# M700E.net
KiCad netlist of a schematic drawn in EAGLE
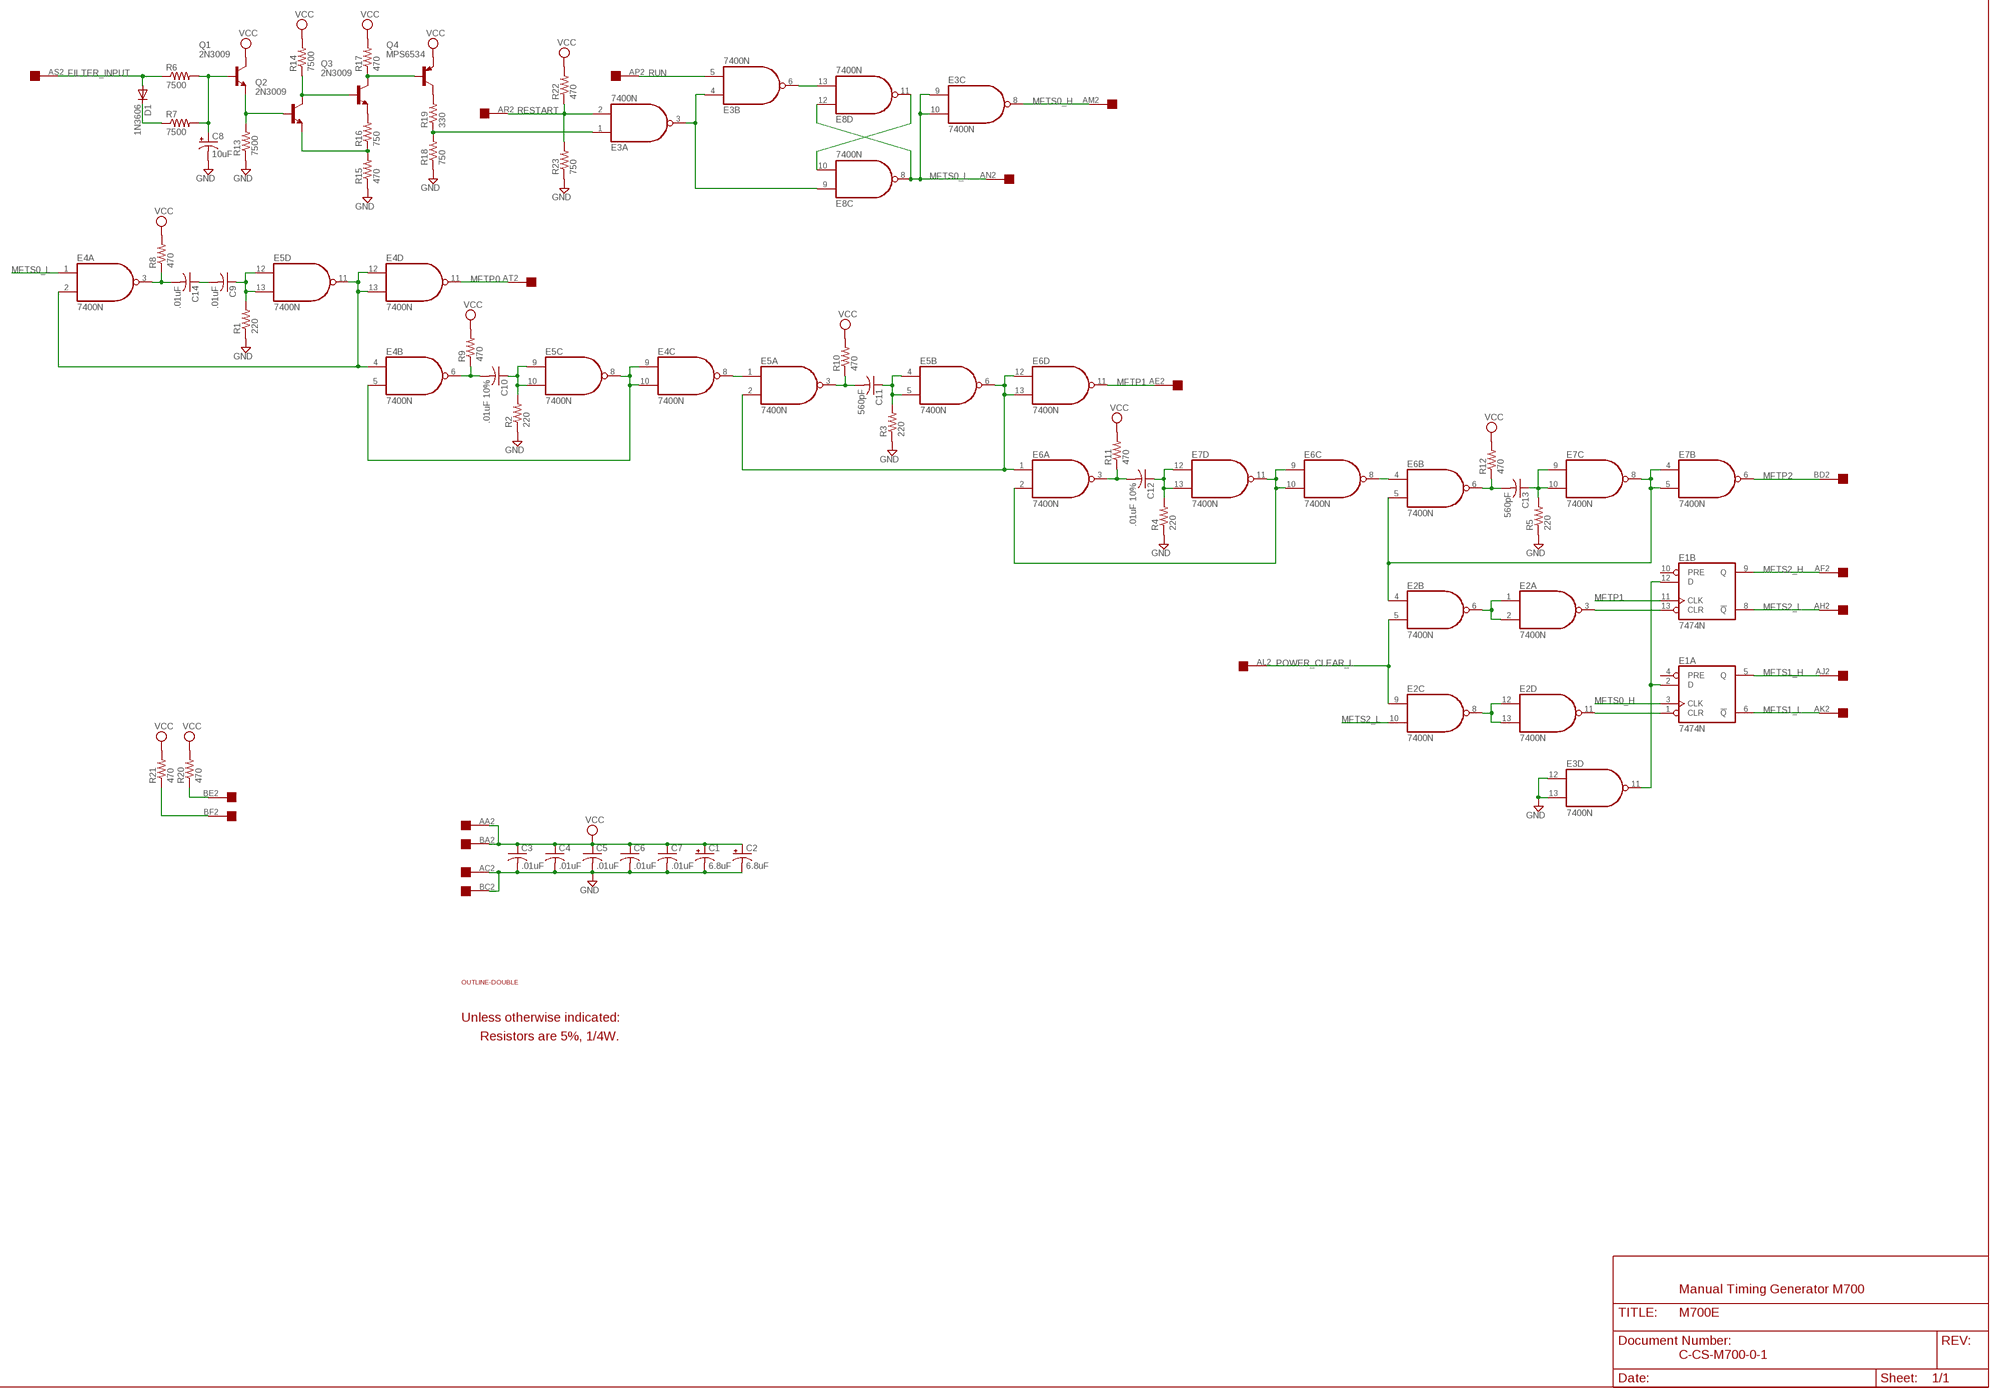
[diagram p0: schematic, sheet 1]

(export (version "E")
  (design (tool "Eeschema 10.0.6"))
  (components
    (comp (ref "C1")
      (value "6.8uF")
      (footprint "eagle-import:E12-8")
      (libsource (lib "eagle-import") (part "CPOL-USE20-8AXIAL"))
    )
    (comp (ref "C2")
      (value "6.8uF")
      (footprint "eagle-import:E12-8")
      (libsource (lib "eagle-import") (part "CPOL-USE20-8AXIAL"))
    )
    (comp (ref "C3")
      (value ".01uF")
      (footprint "eagle-import:C050-025X075")
      (libsource (lib "eagle-import") (part "C-US050-025X075"))
    )
    (comp (ref "C4")
      (value ".01uF")
      (footprint "eagle-import:C050-025X075")
      (libsource (lib "eagle-import") (part "C-US050-025X075"))
    )
    (comp (ref "C5")
      (value ".01uF")
      (footprint "eagle-import:C050-025X075")
      (libsource (lib "eagle-import") (part "C-US050-025X075"))
    )
    (comp (ref "C6")
      (value ".01uF")
      (footprint "eagle-import:C050-025X075")
      (libsource (lib "eagle-import") (part "C-US050-025X075"))
    )
    (comp (ref "C7")
      (value ".01uF")
      (footprint "eagle-import:C050-025X075")
      (libsource (lib "eagle-import") (part "C-US050-025X075"))
    )
    (comp (ref "C8")
      (value "10uF")
      (footprint "eagle-import:E12-8")
      (libsource (lib "eagle-import") (part "CPOL-USE20-8AXIAL"))
    )
    (comp (ref "C9")
      (value ".01uF")
      (footprint "eagle-import:C150-054X183")
      (libsource (lib "eagle-import") (part "C-US150-054X183"))
    )
    (comp (ref "C10")
      (value ".01uF 10%")
      (footprint "eagle-import:C150-054X183")
      (libsource (lib "eagle-import") (part "C-US150-054X183"))
    )
    (comp (ref "C11")
      (value "560pF")
      (footprint "eagle-import:C050-025X075")
      (libsource (lib "eagle-import") (part "C-US050-025X075"))
    )
    (comp (ref "C12")
      (value ".01uF 10%")
      (footprint "eagle-import:C150-054X183")
      (libsource (lib "eagle-import") (part "C-US150-054X183"))
    )
    (comp (ref "C13")
      (value "560pF")
      (footprint "eagle-import:C050-025X075")
      (libsource (lib "eagle-import") (part "C-US050-025X075"))
    )
    (comp (ref "C14")
      (value ".01uF")
      (footprint "eagle-import:C150-054X183")
      (libsource (lib "eagle-import") (part "C-US150-054X183"))
    )
    (comp (ref "D1")
      (value "1N3606")
      (footprint "eagle-import:DO35-10")
      (libsource (lib "eagle-import") (part "1N4148DO35-10"))
    )
    (comp (ref "E1")
      (value "7474N")
      (footprint "eagle-import:DIL14")
      (libsource (lib "eagle-import") (part "7474NS"))
    )
    (comp (ref "E2")
      (value "7400N")
      (footprint "eagle-import:DIL14")
      (libsource (lib "eagle-import") (part "7400N"))
    )
    (comp (ref "E3")
      (value "7400N")
      (footprint "eagle-import:DIL14")
      (libsource (lib "eagle-import") (part "7400N"))
    )
    (comp (ref "E4")
      (value "7400N")
      (footprint "eagle-import:DIL14")
      (libsource (lib "eagle-import") (part "7400N"))
    )
    (comp (ref "E5")
      (value "7400N")
      (footprint "eagle-import:DIL14")
      (libsource (lib "eagle-import") (part "7400N"))
    )
    (comp (ref "E6")
      (value "7400N")
      (footprint "eagle-import:DIL14")
      (libsource (lib "eagle-import") (part "7400N"))
    )
    (comp (ref "E7")
      (value "7400N")
      (footprint "eagle-import:DIL14")
      (libsource (lib "eagle-import") (part "7400N"))
    )
    (comp (ref "E8")
      (value "7400N")
      (footprint "eagle-import:DIL14")
      (libsource (lib "eagle-import") (part "7400N"))
    )
    (comp (ref "Q1")
      (value "2N3009")
      (footprint "eagle-import:TO5")
      (libsource (lib "eagle-import") (part "2N2102"))
    )
    (comp (ref "Q2")
      (value "2N3009")
      (footprint "eagle-import:TO5")
      (libsource (lib "eagle-import") (part "2N2102"))
    )
    (comp (ref "Q3")
      (value "2N3009")
      (footprint "eagle-import:TO5")
      (libsource (lib "eagle-import") (part "2N2102"))
    )
    (comp (ref "Q4")
      (value "MPS6534")
      (footprint "eagle-import:TO5")
      (libsource (lib "eagle-import") (part "2N2905"))
    )
    (comp (ref "R1")
      (value "220")
      (footprint "eagle-import:0207_10")
      (libsource (lib "eagle-import") (part "R-US_0207/10"))
    )
    (comp (ref "R2")
      (value "220")
      (footprint "eagle-import:0207_10")
      (libsource (lib "eagle-import") (part "R-US_0207/10"))
    )
    (comp (ref "R3")
      (value "220")
      (footprint "eagle-import:0207_10")
      (libsource (lib "eagle-import") (part "R-US_0207/10"))
    )
    (comp (ref "R4")
      (value "220")
      (footprint "eagle-import:0207_10")
      (libsource (lib "eagle-import") (part "R-US_0207/10"))
    )
    (comp (ref "R5")
      (value "220")
      (footprint "eagle-import:0207_10")
      (libsource (lib "eagle-import") (part "R-US_0207/10"))
    )
    (comp (ref "R6")
      (value "7500")
      (footprint "eagle-import:0207_10")
      (libsource (lib "eagle-import") (part "R-US_0207/10"))
    )
    (comp (ref "R7")
      (value "7500")
      (footprint "eagle-import:0207_10")
      (libsource (lib "eagle-import") (part "R-US_0207/10"))
    )
    (comp (ref "R8")
      (value "470")
      (footprint "eagle-import:0207_10")
      (libsource (lib "eagle-import") (part "R-US_0207/10"))
    )
    (comp (ref "R9")
      (value "470")
      (footprint "eagle-import:0207_10")
      (libsource (lib "eagle-import") (part "R-US_0207/10"))
    )
    (comp (ref "R10")
      (value "470")
      (footprint "eagle-import:0207_10")
      (libsource (lib "eagle-import") (part "R-US_0207/10"))
    )
    (comp (ref "R11")
      (value "470")
      (footprint "eagle-import:0207_10")
      (libsource (lib "eagle-import") (part "R-US_0207/10"))
    )
    (comp (ref "R12")
      (value "470")
      (footprint "eagle-import:0207_10")
      (libsource (lib "eagle-import") (part "R-US_0207/10"))
    )
    (comp (ref "R13")
      (value "7500")
      (footprint "eagle-import:0207_10")
      (libsource (lib "eagle-import") (part "R-US_0207/10"))
    )
    (comp (ref "R14")
      (value "7500")
      (footprint "eagle-import:0207_10")
      (libsource (lib "eagle-import") (part "R-US_0207/10"))
    )
    (comp (ref "R15")
      (value "470")
      (footprint "eagle-import:0207_10")
      (libsource (lib "eagle-import") (part "R-US_0207/10"))
    )
    (comp (ref "R16")
      (value "750")
      (footprint "eagle-import:0207_10")
      (libsource (lib "eagle-import") (part "R-US_0207/10"))
    )
    (comp (ref "R17")
      (value "470")
      (footprint "eagle-import:0207_10")
      (libsource (lib "eagle-import") (part "R-US_0207/10"))
    )
    (comp (ref "R18")
      (value "750")
      (footprint "eagle-import:0207_10")
      (libsource (lib "eagle-import") (part "R-US_0207/10"))
    )
    (comp (ref "R19")
      (value "330")
      (footprint "eagle-import:0207_10")
      (libsource (lib "eagle-import") (part "R-US_0207/10"))
    )
    (comp (ref "R20")
      (value "470")
      (footprint "eagle-import:0207_10")
      (libsource (lib "eagle-import") (part "R-US_0207/10"))
    )
    (comp (ref "R21")
      (value "470")
      (footprint "eagle-import:0207_10")
      (libsource (lib "eagle-import") (part "R-US_0207/10"))
    )
    (comp (ref "R22")
      (value "470")
      (footprint "eagle-import:0207_10")
      (libsource (lib "eagle-import") (part "R-US_0207/10"))
    )
    (comp (ref "R23")
      (value "750")
      (footprint "eagle-import:0207_10")
      (libsource (lib "eagle-import") (part "R-US_0207/10"))
    )
    (comp (ref "U$1")
      (value "DOUBLE")
      (footprint "eagle-import:EDGE-CON4")
      (libsource (lib "eagle-import") (part "DOUBLE"))
    )
    (comp (ref "U$2")
      (value "OUTLINE-DOUBLE")
      (footprint "eagle-import:DOUBLE")
      (libsource (lib "eagle-import") (part "OUTLINE-DOUBLE"))
    )
  )
  (nets
    (net (code "1") (name "/FILTER_INPUT") (class "Default")
      (node (ref "D1") (pin "A") (pinfunction "A_A") (pintype "passive"))
      (node (ref "R6") (pin "1") (pinfunction "1_1") (pintype "passive"))
      (node (ref "U$1") (pin "AS2") (pinfunction "1_AS2") (pintype "bidirectional"))
    )
    (net (code "2") (name "/MFTP0") (class "Default")
      (node (ref "E4") (pin "11") (pinfunction "O_11") (pintype "output"))
      (node (ref "U$1") (pin "AT2") (pinfunction "1_AT2") (pintype "bidirectional"))
    )
    (net (code "3") (name "/MFTP1") (class "Default")
      (node (ref "E1") (pin "11") (pinfunction "CLK_11") (pintype "input"))
      (node (ref "E6") (pin "11") (pinfunction "O_11") (pintype "output"))
      (node (ref "U$1") (pin "AE2") (pinfunction "1_AE2") (pintype "bidirectional"))
    )
    (net (code "4") (name "/MFTP2") (class "Default")
      (node (ref "E7") (pin "6") (pinfunction "O_6") (pintype "output"))
      (node (ref "U$1") (pin "BD2") (pinfunction "1_BD2") (pintype "bidirectional"))
    )
    (net (code "5") (name "/MFTS0_H") (class "Default")
      (node (ref "E1") (pin "3") (pinfunction "CLK_3") (pintype "input"))
      (node (ref "E3") (pin "8") (pinfunction "O_8") (pintype "output"))
      (node (ref "U$1") (pin "AM2") (pinfunction "1_AM2") (pintype "bidirectional"))
    )
    (net (code "6") (name "/MFTS0_L") (class "Default")
      (node (ref "E3") (pin "10") (pinfunction "I1_10") (pintype "input"))
      (node (ref "E3") (pin "9") (pinfunction "I0_9") (pintype "input"))
      (node (ref "E4") (pin "1") (pinfunction "I0_1") (pintype "input"))
      (node (ref "E8") (pin "12") (pinfunction "I0_12") (pintype "input"))
      (node (ref "E8") (pin "8") (pinfunction "O_8") (pintype "output"))
      (node (ref "U$1") (pin "AN2") (pinfunction "1_AN2") (pintype "bidirectional"))
    )
    (net (code "7") (name "/MFTS1_H") (class "Default")
      (node (ref "E1") (pin "5") (pinfunction "Q_5") (pintype "output"))
      (node (ref "U$1") (pin "AJ2") (pinfunction "1_AJ2") (pintype "bidirectional"))
    )
    (net (code "8") (name "/MFTS1_L") (class "Default")
      (node (ref "E1") (pin "6") (pinfunction "~{Q}_6") (pintype "output"))
      (node (ref "U$1") (pin "AK2") (pinfunction "1_AK2") (pintype "bidirectional"))
    )
    (net (code "9") (name "/MFTS2_H") (class "Default")
      (node (ref "E1") (pin "9") (pinfunction "Q_9") (pintype "output"))
      (node (ref "U$1") (pin "AF2") (pinfunction "1_AF2") (pintype "bidirectional"))
    )
    (net (code "10") (name "/MFTS2_L") (class "Default")
      (node (ref "E1") (pin "8") (pinfunction "~{Q}_8") (pintype "output"))
      (node (ref "E2") (pin "10") (pinfunction "I1_10") (pintype "input"))
      (node (ref "U$1") (pin "AH2") (pinfunction "1_AH2") (pintype "bidirectional"))
    )
    (net (code "11") (name "/POWER_CLEAR_L") (class "Default")
      (node (ref "E2") (pin "5") (pinfunction "I1_5") (pintype "input"))
      (node (ref "E2") (pin "9") (pinfunction "I0_9") (pintype "input"))
      (node (ref "U$1") (pin "AL2") (pinfunction "1_AL2") (pintype "bidirectional"))
    )
    (net (code "12") (name "/RESTART") (class "Default")
      (node (ref "E3") (pin "2") (pinfunction "I1_2") (pintype "input"))
      (node (ref "R22") (pin "1") (pinfunction "1_1") (pintype "passive"))
      (node (ref "R23") (pin "2") (pinfunction "2_2") (pintype "passive"))
      (node (ref "U$1") (pin "AR2") (pinfunction "1_AR2") (pintype "bidirectional"))
    )
    (net (code "13") (name "/RUN") (class "Default")
      (node (ref "E3") (pin "5") (pinfunction "I1_5") (pintype "input"))
      (node (ref "U$1") (pin "AP2") (pinfunction "1_AP2") (pintype "bidirectional"))
    )
    (net (code "14") (name "GND") (class "Default")
      (node (ref "C1") (pin "-") (pinfunction "-_-") (pintype "passive"))
      (node (ref "C2") (pin "-") (pinfunction "-_-") (pintype "passive"))
      (node (ref "C3") (pin "2") (pinfunction "2_2") (pintype "passive"))
      (node (ref "C4") (pin "2") (pinfunction "2_2") (pintype "passive"))
      (node (ref "C5") (pin "2") (pinfunction "2_2") (pintype "passive"))
      (node (ref "C6") (pin "2") (pinfunction "2_2") (pintype "passive"))
      (node (ref "C7") (pin "2") (pinfunction "2_2") (pintype "passive"))
      (node (ref "C8") (pin "-") (pinfunction "-_-") (pintype "passive"))
      (node (ref "E3") (pin "12") (pinfunction "I0_12") (pintype "input"))
      (node (ref "E3") (pin "13") (pinfunction "I1_13") (pintype "input"))
      (node (ref "R1") (pin "1") (pinfunction "1_1") (pintype "passive"))
      (node (ref "R13") (pin "1") (pinfunction "1_1") (pintype "passive"))
      (node (ref "R15") (pin "1") (pinfunction "1_1") (pintype "passive"))
      (node (ref "R18") (pin "1") (pinfunction "1_1") (pintype "passive"))
      (node (ref "R2") (pin "1") (pinfunction "1_1") (pintype "passive"))
      (node (ref "R23") (pin "1") (pinfunction "1_1") (pintype "passive"))
      (node (ref "R3") (pin "1") (pinfunction "1_1") (pintype "passive"))
      (node (ref "R4") (pin "1") (pinfunction "1_1") (pintype "passive"))
      (node (ref "R5") (pin "1") (pinfunction "1_1") (pintype "passive"))
      (node (ref "U$1") (pin "AC2") (pinfunction "1_AC2") (pintype "bidirectional"))
      (node (ref "U$1") (pin "BC2") (pinfunction "1_BC2") (pintype "bidirectional"))
    )
    (net (code "15") (name "Net-(C14-Pad1)") (class "Default")
      (node (ref "C14") (pin "1") (pinfunction "1_1") (pintype "passive"))
      (node (ref "C9") (pin "2") (pinfunction "2_2") (pintype "passive"))
    )
    (net (code "16") (name "Net-(D1-PadC)") (class "Default")
      (node (ref "D1") (pin "C") (pinfunction "C_C") (pintype "passive"))
      (node (ref "R7") (pin "1") (pinfunction "1_1") (pintype "passive"))
    )
    (net (code "17") (name "Net-(E1A-CLR)") (class "Default")
      (node (ref "E1") (pin "1") (pinfunction "CLR_1") (pintype "input"))
      (node (ref "E2") (pin "11") (pinfunction "O_11") (pintype "output"))
    )
    (net (code "18") (name "Net-(E1A-D)") (class "Default")
      (node (ref "E1") (pin "12") (pinfunction "D_12") (pintype "input"))
      (node (ref "E1") (pin "2") (pinfunction "D_2") (pintype "input"))
      (node (ref "E3") (pin "11") (pinfunction "O_11") (pintype "output"))
    )
    (net (code "19") (name "Net-(E1B-CLR)") (class "Default")
      (node (ref "E1") (pin "13") (pinfunction "CLR_13") (pintype "input"))
      (node (ref "E2") (pin "3") (pinfunction "O_3") (pintype "output"))
    )
    (net (code "20") (name "Net-(E2A-I0)") (class "Default")
      (node (ref "E2") (pin "1") (pinfunction "I0_1") (pintype "input"))
      (node (ref "E2") (pin "2") (pinfunction "I1_2") (pintype "input"))
      (node (ref "E2") (pin "6") (pinfunction "O_6") (pintype "output"))
    )
    (net (code "21") (name "Net-(E2B-I0)") (class "Default")
      (node (ref "E2") (pin "4") (pinfunction "I0_4") (pintype "input"))
      (node (ref "E6") (pin "5") (pinfunction "I1_5") (pintype "input"))
      (node (ref "E7") (pin "4") (pinfunction "I0_4") (pintype "input"))
      (node (ref "E7") (pin "5") (pinfunction "I1_5") (pintype "input"))
      (node (ref "E7") (pin "8") (pinfunction "O_8") (pintype "output"))
    )
    (net (code "22") (name "Net-(E2C-O)") (class "Default")
      (node (ref "E2") (pin "12") (pinfunction "I0_12") (pintype "input"))
      (node (ref "E2") (pin "13") (pinfunction "I1_13") (pintype "input"))
      (node (ref "E2") (pin "8") (pinfunction "O_8") (pintype "output"))
    )
    (net (code "23") (name "Net-(E3A-I0)") (class "Default")
      (node (ref "E3") (pin "1") (pinfunction "I0_1") (pintype "input"))
      (node (ref "R18") (pin "2") (pinfunction "2_2") (pintype "passive"))
      (node (ref "R19") (pin "1") (pinfunction "1_1") (pintype "passive"))
    )
    (net (code "24") (name "Net-(E3A-O)") (class "Default")
      (node (ref "E3") (pin "3") (pinfunction "O_3") (pintype "output"))
      (node (ref "E3") (pin "4") (pinfunction "I0_4") (pintype "input"))
      (node (ref "E8") (pin "9") (pinfunction "I0_9") (pintype "input"))
    )
    (net (code "25") (name "Net-(E3B-O)") (class "Default")
      (node (ref "E3") (pin "6") (pinfunction "O_6") (pintype "output"))
      (node (ref "E8") (pin "13") (pinfunction "I1_13") (pintype "input"))
    )
    (net (code "26") (name "Net-(E4A-I1)") (class "Default")
      (node (ref "E4") (pin "12") (pinfunction "I0_12") (pintype "input"))
      (node (ref "E4") (pin "13") (pinfunction "I1_13") (pintype "input"))
      (node (ref "E4") (pin "2") (pinfunction "I1_2") (pintype "input"))
      (node (ref "E4") (pin "4") (pinfunction "I0_4") (pintype "input"))
      (node (ref "E5") (pin "11") (pinfunction "O_11") (pintype "output"))
    )
    (net (code "27") (name "Net-(E4A-O)") (class "Default")
      (node (ref "C14") (pin "2") (pinfunction "2_2") (pintype "passive"))
      (node (ref "E4") (pin "3") (pinfunction "O_3") (pintype "output"))
      (node (ref "R8") (pin "1") (pinfunction "1_1") (pintype "passive"))
    )
    (net (code "28") (name "Net-(E4B-I1)") (class "Default")
      (node (ref "E4") (pin "10") (pinfunction "I1_10") (pintype "input"))
      (node (ref "E4") (pin "5") (pinfunction "I1_5") (pintype "input"))
      (node (ref "E4") (pin "9") (pinfunction "I0_9") (pintype "input"))
      (node (ref "E5") (pin "8") (pinfunction "O_8") (pintype "output"))
    )
    (net (code "29") (name "Net-(E4B-O)") (class "Default")
      (node (ref "C10") (pin "2") (pinfunction "2_2") (pintype "passive"))
      (node (ref "E4") (pin "6") (pinfunction "O_6") (pintype "output"))
      (node (ref "R9") (pin "1") (pinfunction "1_1") (pintype "passive"))
    )
    (net (code "30") (name "Net-(E4C-O)") (class "Default")
      (node (ref "E4") (pin "8") (pinfunction "O_8") (pintype "output"))
      (node (ref "E5") (pin "1") (pinfunction "I0_1") (pintype "input"))
    )
    (net (code "31") (name "Net-(E5A-I1)") (class "Default")
      (node (ref "E5") (pin "2") (pinfunction "I1_2") (pintype "input"))
      (node (ref "E5") (pin "6") (pinfunction "O_6") (pintype "output"))
      (node (ref "E6") (pin "1") (pinfunction "I0_1") (pintype "input"))
      (node (ref "E6") (pin "12") (pinfunction "I0_12") (pintype "input"))
      (node (ref "E6") (pin "13") (pinfunction "I1_13") (pintype "input"))
    )
    (net (code "32") (name "Net-(E5A-O)") (class "Default")
      (node (ref "C11") (pin "2") (pinfunction "2_2") (pintype "passive"))
      (node (ref "E5") (pin "3") (pinfunction "O_3") (pintype "output"))
      (node (ref "R10") (pin "1") (pinfunction "1_1") (pintype "passive"))
    )
    (net (code "33") (name "Net-(E5B-I0)") (class "Default")
      (node (ref "C11") (pin "1") (pinfunction "1_1") (pintype "passive"))
      (node (ref "E5") (pin "4") (pinfunction "I0_4") (pintype "input"))
      (node (ref "E5") (pin "5") (pinfunction "I1_5") (pintype "input"))
      (node (ref "R3") (pin "2") (pinfunction "2_2") (pintype "passive"))
    )
    (net (code "34") (name "Net-(E5C-I0)") (class "Default")
      (node (ref "C10") (pin "1") (pinfunction "1_1") (pintype "passive"))
      (node (ref "E5") (pin "10") (pinfunction "I1_10") (pintype "input"))
      (node (ref "E5") (pin "9") (pinfunction "I0_9") (pintype "input"))
      (node (ref "R2") (pin "2") (pinfunction "2_2") (pintype "passive"))
    )
    (net (code "35") (name "Net-(E5D-I0)") (class "Default")
      (node (ref "C9") (pin "1") (pinfunction "1_1") (pintype "passive"))
      (node (ref "E5") (pin "12") (pinfunction "I0_12") (pintype "input"))
      (node (ref "E5") (pin "13") (pinfunction "I1_13") (pintype "input"))
      (node (ref "R1") (pin "2") (pinfunction "2_2") (pintype "passive"))
    )
    (net (code "36") (name "Net-(E6A-I1)") (class "Default")
      (node (ref "E6") (pin "10") (pinfunction "I1_10") (pintype "input"))
      (node (ref "E6") (pin "2") (pinfunction "I1_2") (pintype "input"))
      (node (ref "E6") (pin "9") (pinfunction "I0_9") (pintype "input"))
      (node (ref "E7") (pin "11") (pinfunction "O_11") (pintype "output"))
    )
    (net (code "37") (name "Net-(E6A-O)") (class "Default")
      (node (ref "C12") (pin "2") (pinfunction "2_2") (pintype "passive"))
      (node (ref "E6") (pin "3") (pinfunction "O_3") (pintype "output"))
      (node (ref "R11") (pin "1") (pinfunction "1_1") (pintype "passive"))
    )
    (net (code "38") (name "Net-(E6B-I0)") (class "Default")
      (node (ref "E6") (pin "4") (pinfunction "I0_4") (pintype "input"))
      (node (ref "E6") (pin "8") (pinfunction "O_8") (pintype "output"))
    )
    (net (code "39") (name "Net-(E6B-O)") (class "Default")
      (node (ref "C13") (pin "2") (pinfunction "2_2") (pintype "passive"))
      (node (ref "E6") (pin "6") (pinfunction "O_6") (pintype "output"))
      (node (ref "R12") (pin "1") (pinfunction "1_1") (pintype "passive"))
    )
    (net (code "40") (name "Net-(E7C-I0)") (class "Default")
      (node (ref "C13") (pin "1") (pinfunction "1_1") (pintype "passive"))
      (node (ref "E7") (pin "10") (pinfunction "I1_10") (pintype "input"))
      (node (ref "E7") (pin "9") (pinfunction "I0_9") (pintype "input"))
      (node (ref "R5") (pin "2") (pinfunction "2_2") (pintype "passive"))
    )
    (net (code "41") (name "Net-(E7D-I0)") (class "Default")
      (node (ref "C12") (pin "1") (pinfunction "1_1") (pintype "passive"))
      (node (ref "E7") (pin "12") (pinfunction "I0_12") (pintype "input"))
      (node (ref "E7") (pin "13") (pinfunction "I1_13") (pintype "input"))
      (node (ref "R4") (pin "2") (pinfunction "2_2") (pintype "passive"))
    )
    (net (code "42") (name "Net-(E8C-I1)") (class "Default")
      (node (ref "E8") (pin "10") (pinfunction "I1_10") (pintype "input"))
      (node (ref "E8") (pin "11") (pinfunction "O_11") (pintype "output"))
    )
    (net (code "43") (name "Net-(Q1-B)") (class "Default")
      (node (ref "C8") (pin "+") (pinfunction "+_+") (pintype "passive"))
      (node (ref "Q1") (pin "2") (pinfunction "B_2") (pintype "passive"))
      (node (ref "R6") (pin "2") (pinfunction "2_2") (pintype "passive"))
      (node (ref "R7") (pin "2") (pinfunction "2_2") (pintype "passive"))
    )
    (net (code "44") (name "Net-(Q1-E)") (class "Default")
      (node (ref "Q1") (pin "1") (pinfunction "E_1") (pintype "passive"))
      (node (ref "Q2") (pin "2") (pinfunction "B_2") (pintype "passive"))
      (node (ref "R13") (pin "2") (pinfunction "2_2") (pintype "passive"))
    )
    (net (code "45") (name "Net-(Q2-C)") (class "Default")
      (node (ref "Q2") (pin "3") (pinfunction "C_3") (pintype "passive"))
      (node (ref "Q3") (pin "2") (pinfunction "B_2") (pintype "passive"))
      (node (ref "R14") (pin "1") (pinfunction "1_1") (pintype "passive"))
    )
    (net (code "46") (name "Net-(Q2-E)") (class "Default")
      (node (ref "Q2") (pin "1") (pinfunction "E_1") (pintype "passive"))
      (node (ref "R15") (pin "2") (pinfunction "2_2") (pintype "passive"))
      (node (ref "R16") (pin "1") (pinfunction "1_1") (pintype "passive"))
    )
    (net (code "47") (name "Net-(Q3-C)") (class "Default")
      (node (ref "Q3") (pin "3") (pinfunction "C_3") (pintype "passive"))
      (node (ref "Q4") (pin "2") (pinfunction "B_2") (pintype "passive"))
      (node (ref "R17") (pin "1") (pinfunction "1_1") (pintype "passive"))
    )
    (net (code "48") (name "Net-(Q3-E)") (class "Default")
      (node (ref "Q3") (pin "1") (pinfunction "E_1") (pintype "passive"))
      (node (ref "R16") (pin "2") (pinfunction "2_2") (pintype "passive"))
    )
    (net (code "49") (name "Net-(Q4-C)") (class "Default")
      (node (ref "Q4") (pin "3") (pinfunction "C_3") (pintype "passive"))
      (node (ref "R19") (pin "2") (pinfunction "2_2") (pintype "passive"))
    )
    (net (code "50") (name "Net-(U$1AT-1)") (class "Default")
      (node (ref "R20") (pin "1") (pinfunction "1_1") (pintype "passive"))
      (node (ref "U$1") (pin "BE2") (pinfunction "1_BE2") (pintype "bidirectional"))
    )
    (net (code "51") (name "Net-(U$1AV-1)") (class "Default")
      (node (ref "R21") (pin "1") (pinfunction "1_1") (pintype "passive"))
      (node (ref "U$1") (pin "BF2") (pinfunction "1_BF2") (pintype "bidirectional"))
    )
    (net (code "52") (name "VCC") (class "Default")
      (node (ref "C1") (pin "+") (pinfunction "+_+") (pintype "passive"))
      (node (ref "C2") (pin "+") (pinfunction "+_+") (pintype "passive"))
      (node (ref "C3") (pin "1") (pinfunction "1_1") (pintype "passive"))
      (node (ref "C4") (pin "1") (pinfunction "1_1") (pintype "passive"))
      (node (ref "C5") (pin "1") (pinfunction "1_1") (pintype "passive"))
      (node (ref "C6") (pin "1") (pinfunction "1_1") (pintype "passive"))
      (node (ref "C7") (pin "1") (pinfunction "1_1") (pintype "passive"))
      (node (ref "Q1") (pin "3") (pinfunction "C_3") (pintype "passive"))
      (node (ref "Q4") (pin "1") (pinfunction "E_1") (pintype "passive"))
      (node (ref "R10") (pin "2") (pinfunction "2_2") (pintype "passive"))
      (node (ref "R11") (pin "2") (pinfunction "2_2") (pintype "passive"))
      (node (ref "R12") (pin "2") (pinfunction "2_2") (pintype "passive"))
      (node (ref "R14") (pin "2") (pinfunction "2_2") (pintype "passive"))
      (node (ref "R17") (pin "2") (pinfunction "2_2") (pintype "passive"))
      (node (ref "R20") (pin "2") (pinfunction "2_2") (pintype "passive"))
      (node (ref "R21") (pin "2") (pinfunction "2_2") (pintype "passive"))
      (node (ref "R22") (pin "2") (pinfunction "2_2") (pintype "passive"))
      (node (ref "R8") (pin "2") (pinfunction "2_2") (pintype "passive"))
      (node (ref "R9") (pin "2") (pinfunction "2_2") (pintype "passive"))
      (node (ref "U$1") (pin "AA2") (pinfunction "1_AA2") (pintype "bidirectional"))
      (node (ref "U$1") (pin "BA2") (pinfunction "1_BA2") (pintype "bidirectional"))
    )
    (net (code "53") (name "unconnected-(E1A-PRE-Pad4)") (class "Default")
      (node (ref "E1") (pin "4") (pinfunction "PRE_4") (pintype "input"))
    )
    (net (code "54") (name "unconnected-(E1B-PRE-Pad10)") (class "Default")
      (node (ref "E1") (pin "10") (pinfunction "PRE_10") (pintype "input"))
    )
  )
)
